# ESP8266EX.net
KiCad netlist of a schematic drawn in Altium Designer
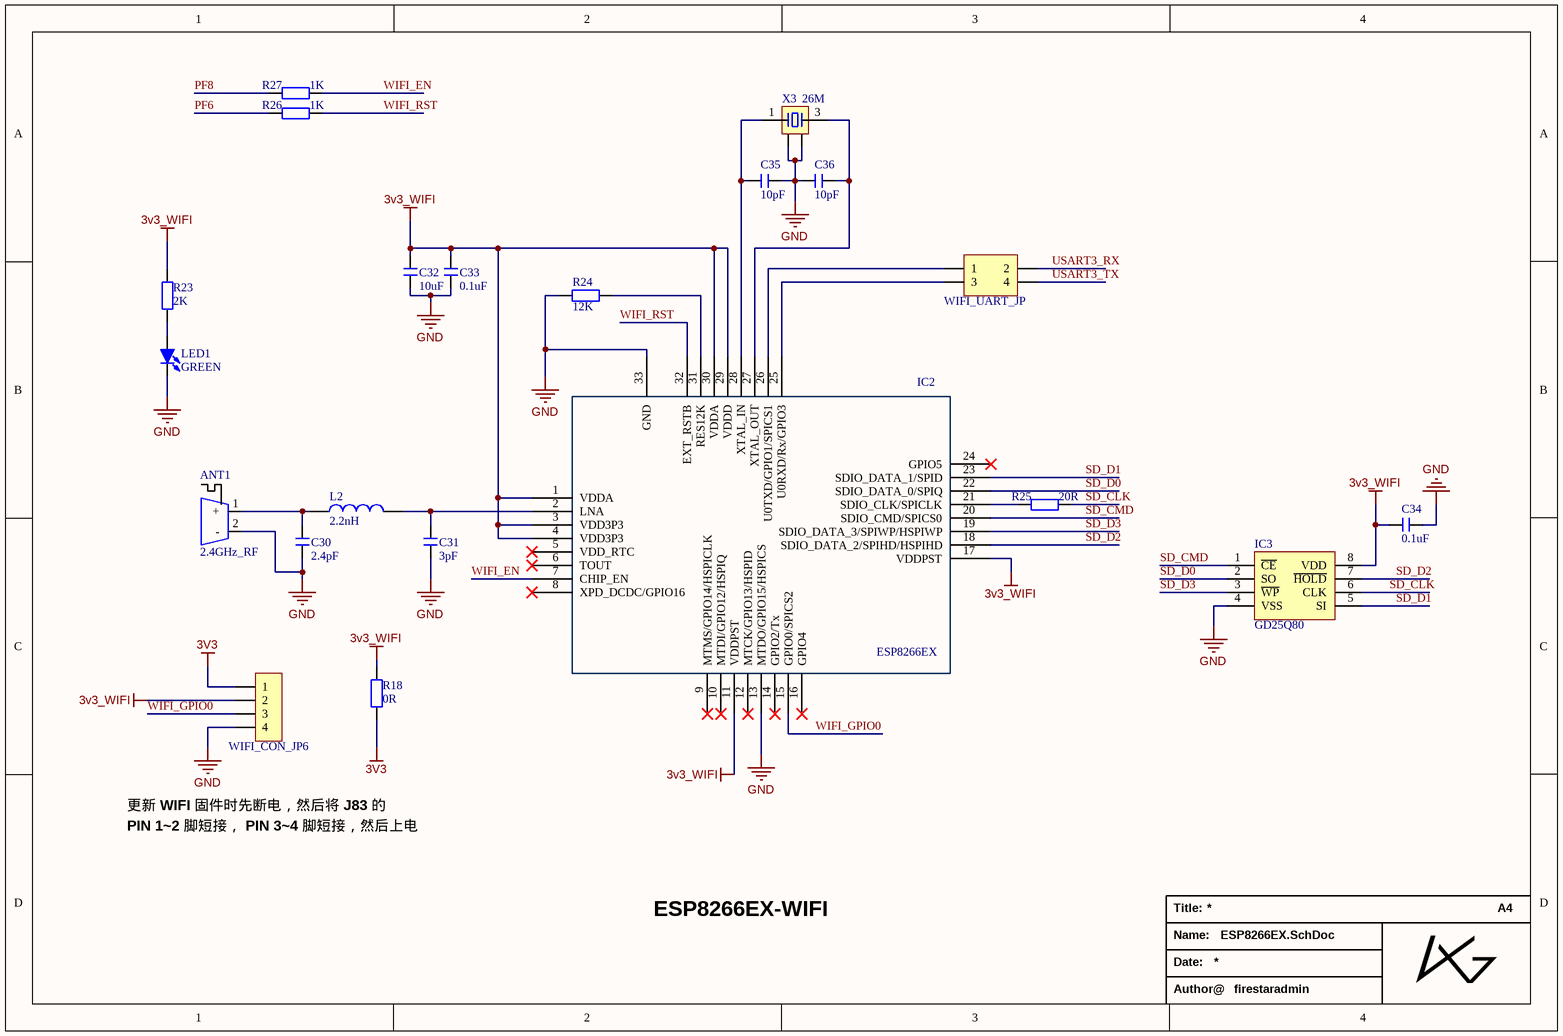
[diagram p0: ESP8266EX.SchDoc]

(export (version "E")
  (design (tool "Eeschema 10.0.6"))
  (components
    (comp (ref "ANT1")
      (value "2.4GHz_RF")
      (footprint "ANT-F-1-2.4G")
      (libsource (lib "altium-import") (part "root_0_2.4GHz_RF_"))
    )
    (comp (ref "C30")
      (value "2.4pF")
      (footprint "C 0603_M")
      (description "无极性贴片电容")
      (fields (field (name "版权归属") "源创客"))
      (libsource (lib "altium-import") (part "root_3_C_"))
    )
    (comp (ref "C31")
      (value "3pF")
      (footprint "C 0603_M")
      (description "无极性贴片电容")
      (fields (field (name "版权归属") "源创客"))
      (libsource (lib "altium-import") (part "root_3_C_"))
    )
    (comp (ref "C32")
      (value "10uF")
      (footprint "C 0603_M")
      (description "无极性贴片电容")
      (fields (field (name "版权归属") "源创客"))
      (libsource (lib "altium-import") (part "root_3_C_"))
    )
    (comp (ref "C33")
      (value "0.1uF")
      (footprint "C 0603_M")
      (description "无极性贴片电容")
      (fields (field (name "版权归属") "源创客"))
      (libsource (lib "altium-import") (part "root_3_C_"))
    )
    (comp (ref "C34")
      (value "0.1uF")
      (footprint "C 0603_M")
      (description "无极性贴片电容")
      (fields (field (name "版权归属") "源创客"))
      (libsource (lib "altium-import") (part "root_0_C_"))
    )
    (comp (ref "C35")
      (value "10pF")
      (footprint "C 0603_M")
      (description "无极性贴片电容")
      (fields (field (name "版权归属") "源创客"))
      (libsource (lib "altium-import") (part "root_2_C_"))
    )
    (comp (ref "C36")
      (value "10pF")
      (footprint "C 0603_M")
      (description "无极性贴片电容")
      (fields (field (name "版权归属") "源创客"))
      (libsource (lib "altium-import") (part "root_2_C_"))
    )
    (comp (ref "IC2")
      (value "ESP8266EX")
      (footprint "QFN32 5x5_L")
      (description "WIFI-芯片")
      (fields (field (name "版权归属") "源创客"))
      (libsource (lib "altium-import") (part "root_0_ESP8266EX_"))
    )
    (comp (ref "IC3")
      (value "GD25Q80")
      (footprint "SOP8W_N")
      (description "外置Flash")
      (fields (field (name "版权归属") "源创客"))
      (libsource (lib "altium-import") (part "root_0_SST25VFxx_"))
    )
    (comp (ref "L2")
      (value "2.2nH")
      (footprint "L 0603")
      (description "小功率贴片电感")
      (fields (field (name "版权归属") "源创客"))
      (libsource (lib "altium-import") (part "root_0_L_"))
    )
    (comp (ref "LED1")
      (value "GREEN")
      (footprint "LED 0603G")
      (description "贴片LED")
      (fields (field (name "版权归属") "源创客"))
      (libsource (lib "altium-import") (part "root_0_LED-SMD_"))
    )
    (comp (ref "R18")
      (value "0R")
      (footprint "R 0603_M")
      (description "Resistor")
      (libsource (lib "General") (part "RES"))
    )
    (comp (ref "R23")
      (value "2K")
      (footprint "R 0603_M")
      (description "Resistor")
      (libsource (lib "General") (part "RES"))
    )
    (comp (ref "R24")
      (value "12K")
      (footprint "R 0603_M")
      (description "Resistor")
      (libsource (lib "") (part "RES_1"))
    )
    (comp (ref "R25")
      (value "20R")
      (footprint "R 0603_M")
      (description "Resistor")
      (libsource (lib "") (part "RES_1"))
    )
    (comp (ref "R26")
      (value "1K")
      (footprint "R 0603_M")
      (description "Resistor")
      (libsource (lib "") (part "RES_1"))
    )
    (comp (ref "R27")
      (value "1K")
      (footprint "R 0603_M")
      (description "Resistor")
      (libsource (lib "") (part "RES_1"))
    )
    (comp (ref "WIFI_CON_JP6")
      (value "HDR-1X4")
      (footprint "HDR2.54-LI-4P")
      (description "4P接插件")
      (fields (field (name "版权归属") "源创客"))
      (libsource (lib "altium-import") (part "root_0_Header 4_"))
    )
    (comp (ref "WIFI_UART_JP")
      (value "Header2X2")
      (footprint "HDR2.54-LI-2x2P")
      (description "2*2P接插件")
      (fields (field (name "版权归属") "源创客"))
      (libsource (lib "4.5   - 接插件-脚距2.54") (part "Header 2X2"))
    )
    (comp (ref "X3")
      (value "26M")
      (footprint "OSC 3225-4P")
      (description "4脚无源晶振")
      (fields (field (name "版权归属") "源创客"))
      (libsource (lib "altium-import") (part "root_0_XTAL-4P_"))
    )
  )
  (nets
    (net (code "1") (name "/PF6") (class "Default")
      (node (ref "R26") (pin "2") (pinfunction "2_2") (pintype "passive"))
    )
    (net (code "2") (name "/PF8") (class "Default")
      (node (ref "R27") (pin "2") (pinfunction "2_2") (pintype "passive"))
    )
    (net (code "3") (name "/SD_CLK") (class "Default")
      (node (ref "IC3") (pin "6") (pinfunction "CLK_6") (pintype "passive"))
      (node (ref "R25") (pin "1") (pinfunction "1_1") (pintype "passive"))
    )
    (net (code "4") (name "/SD_CMD") (class "Default")
      (node (ref "IC2") (pin "20") (pinfunction "SDIO_CMD/SPICS0_20") (pintype "passive"))
      (node (ref "IC3") (pin "1") (pinfunction "~{CE}_1") (pintype "passive"))
    )
    (net (code "5") (name "/SD_D0") (class "Default")
      (node (ref "IC2") (pin "22") (pinfunction "SDIO_DATA_0/SPIQ_22") (pintype "passive"))
      (node (ref "IC3") (pin "2") (pinfunction "SO_2") (pintype "passive"))
    )
    (net (code "6") (name "/SD_D1") (class "Default")
      (node (ref "IC2") (pin "23") (pinfunction "SDIO_DATA_1/SPID_23") (pintype "passive"))
      (node (ref "IC3") (pin "5") (pinfunction "SI_5") (pintype "passive"))
    )
    (net (code "7") (name "/SD_D2") (class "Default")
      (node (ref "IC2") (pin "18") (pinfunction "SDIO_DATA_2/SPIHD/HSPIHD_18") (pintype "passive"))
      (node (ref "IC3") (pin "7") (pinfunction "~{HOLD}_7") (pintype "passive"))
    )
    (net (code "8") (name "/SD_D3") (class "Default")
      (node (ref "IC2") (pin "19") (pinfunction "SDIO_DATA_3/SPIWP/HSPIWP_19") (pintype "passive"))
      (node (ref "IC3") (pin "3") (pinfunction "~{WP}_3") (pintype "passive"))
    )
    (net (code "9") (name "/USART3_RX") (class "Default")
      (node (ref "WIFI_UART_JP") (pin "2") (pinfunction "2_2") (pintype "passive"))
    )
    (net (code "10") (name "/USART3_TX") (class "Default")
      (node (ref "WIFI_UART_JP") (pin "4") (pinfunction "4_4") (pintype "passive"))
    )
    (net (code "11") (name "/WIFI_EN") (class "Default")
      (node (ref "IC2") (pin "7") (pinfunction "CHIP_EN_7") (pintype "passive"))
      (node (ref "R27") (pin "1") (pinfunction "1_1") (pintype "passive"))
    )
    (net (code "12") (name "/WIFI_GPIO0") (class "Default")
      (node (ref "IC2") (pin "15") (pinfunction "GPIO0/SPICS2_15") (pintype "passive"))
      (node (ref "WIFI_CON_JP6") (pin "3") (pinfunction "3_3") (pintype "passive"))
    )
    (net (code "13") (name "/WIFI_RST") (class "Default")
      (node (ref "IC2") (pin "32") (pinfunction "EXT_RSTB_32") (pintype "passive"))
      (node (ref "R26") (pin "1") (pinfunction "1_1") (pintype "passive"))
    )
    (net (code "14") (name "3V3") (class "Default")
      (node (ref "R18") (pin "1") (pinfunction "1_1") (pintype "passive"))
      (node (ref "WIFI_CON_JP6") (pin "1") (pinfunction "1_1") (pintype "passive"))
    )
    (net (code "15") (name "3v3_WIFI") (class "Default")
      (node (ref "C32") (pin "1") (pinfunction "1_1") (pintype "passive"))
      (node (ref "C33") (pin "1") (pinfunction "1_1") (pintype "passive"))
      (node (ref "C34") (pin "1") (pinfunction "1_1") (pintype "passive"))
      (node (ref "IC2") (pin "1") (pinfunction "VDDA_1") (pintype "passive"))
      (node (ref "IC2") (pin "11") (pinfunction "VDDPST_11") (pintype "passive"))
      (node (ref "IC2") (pin "17") (pinfunction "VDDPST_17") (pintype "passive"))
      (node (ref "IC2") (pin "29") (pinfunction "VDDD_29") (pintype "passive"))
      (node (ref "IC2") (pin "3") (pinfunction "VDD3P3_3") (pintype "passive"))
      (node (ref "IC2") (pin "30") (pinfunction "VDDA_30") (pintype "passive"))
      (node (ref "IC2") (pin "4") (pinfunction "VDD3P3_4") (pintype "passive"))
      (node (ref "IC3") (pin "8") (pinfunction "VDD_8") (pintype "passive"))
      (node (ref "R18") (pin "2") (pinfunction "2_2") (pintype "passive"))
      (node (ref "R23") (pin "2") (pinfunction "2_2") (pintype "passive"))
      (node (ref "WIFI_CON_JP6") (pin "2") (pinfunction "2_2") (pintype "passive"))
    )
    (net (code "16") (name "GND") (class "Default")
      (node (ref "ANT1") (pin "2") (pinfunction "-_2") (pintype "passive"))
      (node (ref "C30") (pin "2") (pinfunction "2_2") (pintype "passive"))
      (node (ref "C31") (pin "2") (pinfunction "2_2") (pintype "passive"))
      (node (ref "C32") (pin "2") (pinfunction "2_2") (pintype "passive"))
      (node (ref "C33") (pin "2") (pinfunction "2_2") (pintype "passive"))
      (node (ref "C34") (pin "2") (pinfunction "2_2") (pintype "passive"))
      (node (ref "C35") (pin "1") (pinfunction "1_1") (pintype "passive"))
      (node (ref "C36") (pin "2") (pinfunction "2_2") (pintype "passive"))
      (node (ref "IC2") (pin "13") (pinfunction "MTDO/GPIO15/HSPICS_13") (pintype "passive"))
      (node (ref "IC2") (pin "33") (pinfunction "GND_33") (pintype "passive"))
      (node (ref "IC3") (pin "4") (pinfunction "VSS_4") (pintype "passive"))
      (node (ref "LED1") (pin "2") (pinfunction "K_2") (pintype "passive"))
      (node (ref "R24") (pin "2") (pinfunction "2_2") (pintype "passive"))
      (node (ref "WIFI_CON_JP6") (pin "4") (pinfunction "4_4") (pintype "passive"))
      (node (ref "X3") (pin "2") (pinfunction "2_2") (pintype "passive"))
      (node (ref "X3") (pin "4") (pinfunction "4_4") (pintype "passive"))
    )
    (net (code "17") (name "Net-(ANT1-+)") (class "Default")
      (node (ref "ANT1") (pin "1") (pinfunction "+_1") (pintype "passive"))
      (node (ref "C30") (pin "1") (pinfunction "1_1") (pintype "passive"))
      (node (ref "L2") (pin "1") (pinfunction "1_1") (pintype "passive"))
    )
    (net (code "18") (name "Net-(IC2-LNA)") (class "Default")
      (node (ref "C31") (pin "1") (pinfunction "1_1") (pintype "passive"))
      (node (ref "IC2") (pin "2") (pinfunction "LNA_2") (pintype "passive"))
      (node (ref "L2") (pin "2") (pinfunction "2_2") (pintype "passive"))
    )
    (net (code "19") (name "Net-(IC2-RES12K)") (class "Default")
      (node (ref "IC2") (pin "31") (pinfunction "RES12K_31") (pintype "passive"))
      (node (ref "R24") (pin "1") (pinfunction "1_1") (pintype "passive"))
    )
    (net (code "20") (name "Net-(IC2-SDIO_CLK{slash}SPICLK)") (class "Default")
      (node (ref "IC2") (pin "21") (pinfunction "SDIO_CLK/SPICLK_21") (pintype "passive"))
      (node (ref "R25") (pin "2") (pinfunction "2_2") (pintype "passive"))
    )
    (net (code "21") (name "Net-(IC2-U0RXD{slash}Rx{slash}GPIO3)") (class "Default")
      (node (ref "IC2") (pin "25") (pinfunction "U0RXD/Rx/GPIO3_25") (pintype "passive"))
      (node (ref "WIFI_UART_JP") (pin "3") (pinfunction "3_3") (pintype "passive"))
    )
    (net (code "22") (name "Net-(IC2-U0TXD{slash}GPIO1{slash}SPICS1)") (class "Default")
      (node (ref "IC2") (pin "26") (pinfunction "U0TXD/GPIO1/SPICS1_26") (pintype "passive"))
      (node (ref "WIFI_UART_JP") (pin "1") (pinfunction "1_1") (pintype "passive"))
    )
    (net (code "23") (name "Net-(IC2-XTAL_IN)") (class "Default")
      (node (ref "C35") (pin "2") (pinfunction "2_2") (pintype "passive"))
      (node (ref "IC2") (pin "28") (pinfunction "XTAL_IN_28") (pintype "passive"))
      (node (ref "X3") (pin "1") (pinfunction "1_1") (pintype "passive"))
    )
    (net (code "24") (name "Net-(IC2-XTAL_OUT)") (class "Default")
      (node (ref "C36") (pin "1") (pinfunction "1_1") (pintype "passive"))
      (node (ref "IC2") (pin "27") (pinfunction "XTAL_OUT_27") (pintype "passive"))
      (node (ref "X3") (pin "3") (pinfunction "3_3") (pintype "passive"))
    )
    (net (code "25") (name "Net-(LED1-A)") (class "Default")
      (node (ref "LED1") (pin "1") (pinfunction "A_1") (pintype "passive"))
      (node (ref "R23") (pin "1") (pinfunction "1_1") (pintype "passive"))
    )
    (net (code "26") (name "unconnected-(IC2-GPIO2{slash}Tx-Pad14)") (class "Default")
      (node (ref "IC2") (pin "14") (pinfunction "GPIO2/Tx_14") (pintype "passive+no_connect"))
    )
    (net (code "27") (name "unconnected-(IC2-GPIO4-Pad16)") (class "Default")
      (node (ref "IC2") (pin "16") (pinfunction "GPIO4_16") (pintype "passive+no_connect"))
    )
    (net (code "28") (name "unconnected-(IC2-GPIO5-Pad24)") (class "Default")
      (node (ref "IC2") (pin "24") (pinfunction "GPIO5_24") (pintype "passive+no_connect"))
    )
    (net (code "29") (name "unconnected-(IC2-MTCK{slash}GPIO13{slash}HSPID-Pad12)") (class "Default")
      (node (ref "IC2") (pin "12") (pinfunction "MTCK/GPIO13/HSPID_12") (pintype "passive+no_connect"))
    )
    (net (code "30") (name "unconnected-(IC2-MTDI{slash}GPIO12{slash}HSPIQ-Pad10)") (class "Default")
      (node (ref "IC2") (pin "10") (pinfunction "MTDI/GPIO12/HSPIQ_10") (pintype "passive+no_connect"))
    )
    (net (code "31") (name "unconnected-(IC2-MTMS{slash}GPIO14{slash}HSPICLK-Pad9)") (class "Default")
      (node (ref "IC2") (pin "9") (pinfunction "MTMS/GPIO14/HSPICLK_9") (pintype "passive+no_connect"))
    )
    (net (code "32") (name "unconnected-(IC2-TOUT-Pad6)") (class "Default")
      (node (ref "IC2") (pin "6") (pinfunction "TOUT_6") (pintype "passive+no_connect"))
    )
    (net (code "33") (name "unconnected-(IC2-VDD_RTC-Pad5)") (class "Default")
      (node (ref "IC2") (pin "5") (pinfunction "VDD_RTC_5") (pintype "passive+no_connect"))
    )
    (net (code "34") (name "unconnected-(IC2-XPD_DCDC{slash}GPIO16-Pad8)") (class "Default")
      (node (ref "IC2") (pin "8") (pinfunction "XPD_DCDC/GPIO16_8") (pintype "passive+no_connect"))
    )
  )
)
